# 180Micro_TopLevel.net
KiCad netlist of a schematic drawn in Altium Designer
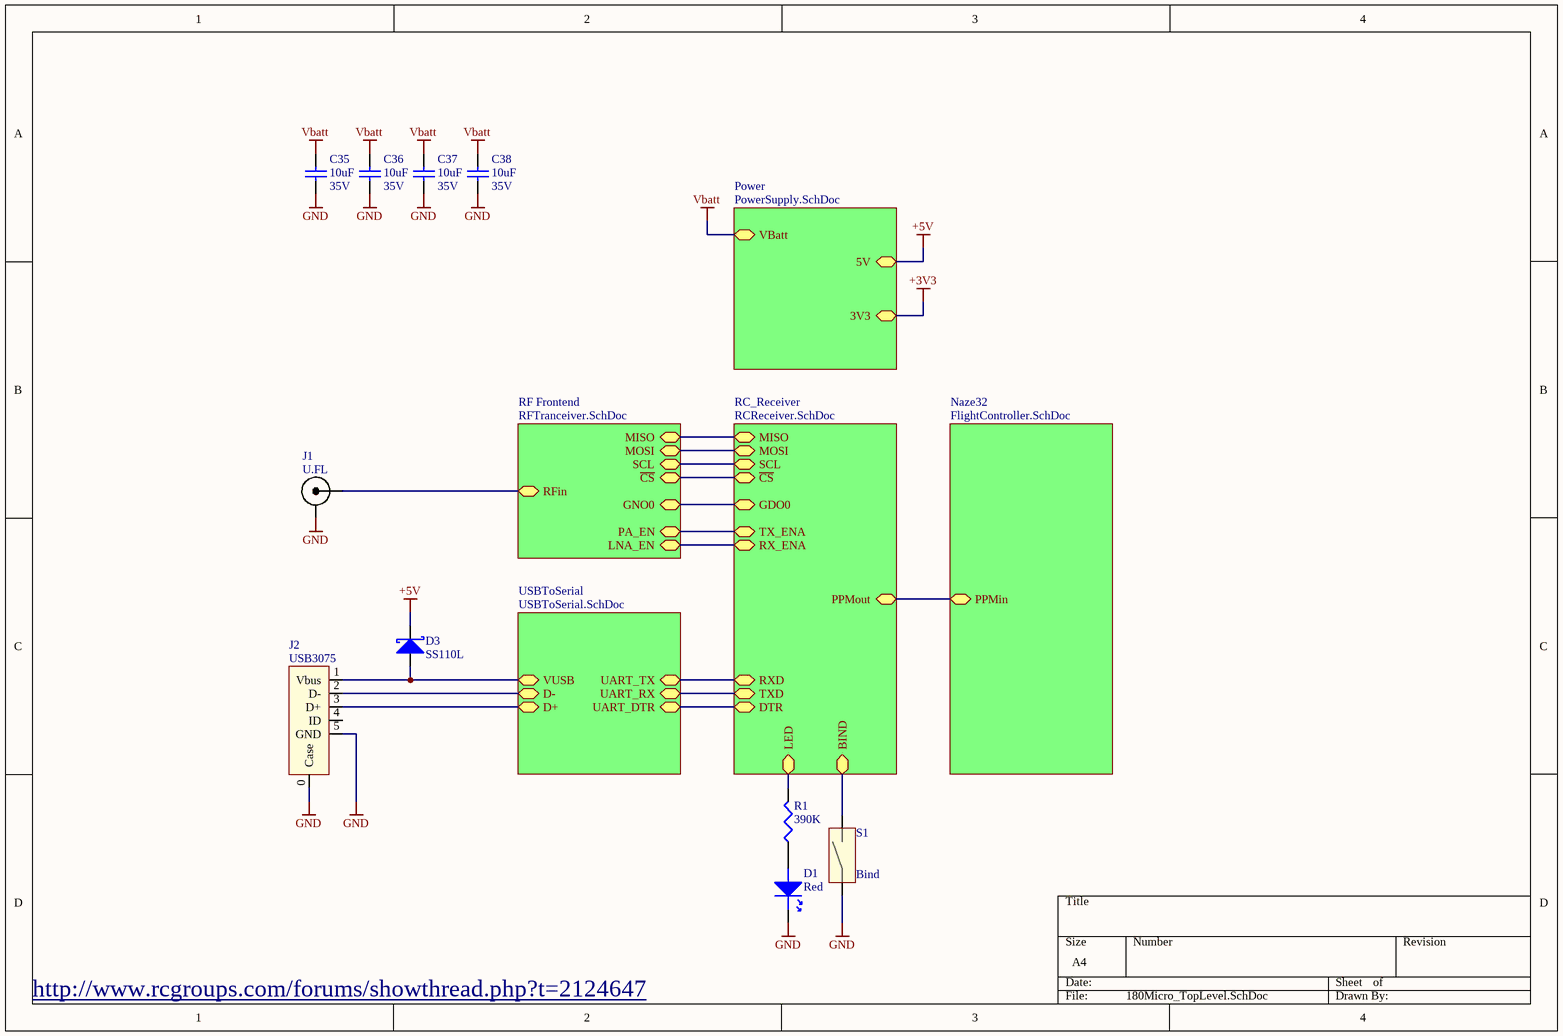
[diagram p0: 180Micro_TopLevel.SchDoc]

(export (version "E")
  (design (tool "Eeschema 10.0.6"))
  (components
    (comp (ref "C35")
      (value "10uF")
      (description "Capacitor, 10uF, 35V, X5R")
      (fields (field (name "VOLTAGE RATING") "35V"))
      (libsource (lib "AR_Capacitors_Ceramic") (part "10uF/1206/CER/35V"))
    )
    (comp (ref "C36")
      (value "10uF")
      (description "Capacitor, 10uF, 35V, X5R")
      (fields (field (name "VOLTAGE RATING") "35V"))
      (libsource (lib "AR_Capacitors_Ceramic") (part "10uF/1206/CER/35V"))
    )
    (comp (ref "C37")
      (value "10uF")
      (description "Capacitor, 10uF, 35V, X5R")
      (fields (field (name "VOLTAGE RATING") "35V"))
      (libsource (lib "AR_Capacitors_Ceramic") (part "10uF/1206/CER/35V"))
    )
    (comp (ref "C38")
      (value "10uF")
      (description "Capacitor, 10uF, 35V, X5R")
      (fields (field (name "VOLTAGE RATING") "35V"))
      (libsource (lib "AR_Capacitors_Ceramic") (part "10uF/1206/CER/35V"))
    )
    (comp (ref "D1")
      (value "Red")
      (footprint "D-0805")
      (description "Led, Red, Li:2.5mcd, Vf:1.8V, If:0.02A")
      (libsource (lib "AR_Misc") (part "SML-211UTT86K"))
    )
    (comp (ref "D3")
      (value "SS110L")
      (footprint "SUB-SMA")
      (description "Diode Schottky, Vrrm: 100V, If: 1A, Vf: 0.9V")
      (libsource (lib "AR_Diodes") (part "SS110L"))
    )
    (comp (ref "J1")
      (value "U.FL")
      (footprint "U_FL")
      (description "Connector RF Coax")
      (libsource (lib "AR_Connectors") (part "U.FL-R-SMT"))
    )
    (comp (ref "J2")
      (value "USB3075")
      (footprint "USB3075")
      (description "USB 2.0 MICRO B, RCPT, 5POS, SMT")
      (libsource (lib "AR_Connectors") (part "USB3075"))
    )
    (comp (ref "R1")
      (value "390K")
      (footprint "0603")
      (description "Resistor, 390K, 1%, 0.1W, 75V, 50PPM, 0603")
      (libsource (lib "AR_Resistors_SMD") (part "390K/0603/0100W/75V"))
    )
    (comp (ref "S1")
      (value "Bind")
      (footprint "KSS")
      (description "Switch, Tactile, SPNO, DC:32V, DC:50mA")
      (libsource (lib "AR_Misc") (part "KSS341G LFS"))
    )
  )
  (nets
    (net (code "2") (name "+5V") (class "Default")
      (node (ref "D3") (pin "2") (pinfunction "K_2") (pintype "passive"))
    )
    (net (code "3") (name "/BIND") (class "Default")
      (node (ref "S1") (pin "2") (pinfunction "2_2") (pintype "passive"))
    )
    (net (code "4") (name "/D+") (class "Default")
      (node (ref "J2") (pin "3") (pinfunction "D+_3") (pintype "passive"))
    )
    (net (code "5") (name "/D-") (class "Default")
      (node (ref "J2") (pin "2") (pinfunction "D-_2") (pintype "passive"))
    )
    (net (code "8") (name "/LED") (class "Default")
      (node (ref "R1") (pin "2") (pinfunction "2_2") (pintype "passive"))
    )
    (net (code "14") (name "/RFin") (class "Default")
      (node (ref "J1") (pin "1") (pinfunction "1_1") (pintype "power_in"))
    )
    (net (code "18") (name "/VUSB") (class "Default")
      (node (ref "D3") (pin "1") (pinfunction "A_1") (pintype "passive"))
      (node (ref "J2") (pin "1") (pinfunction "Vbus_1") (pintype "passive"))
    )
    (net (code "20") (name "GND") (class "Default")
      (node (ref "C35") (pin "1") (pinfunction "1_1") (pintype "passive"))
      (node (ref "C36") (pin "1") (pinfunction "1_1") (pintype "passive"))
      (node (ref "C37") (pin "1") (pinfunction "1_1") (pintype "passive"))
      (node (ref "C38") (pin "1") (pinfunction "1_1") (pintype "passive"))
      (node (ref "D1") (pin "K") (pinfunction "K_K") (pintype "passive"))
      (node (ref "J1") (pin "0") (pinfunction "GND_0") (pintype "power_in"))
      (node (ref "J2") (pin "0") (pinfunction "Case_0") (pintype "passive"))
      (node (ref "J2") (pin "5") (pinfunction "GND_5") (pintype "passive"))
      (node (ref "S1") (pin "1") (pinfunction "1_1") (pintype "passive"))
    )
    (net (code "21") (name "Net-(D1-PadA)") (class "Default")
      (node (ref "D1") (pin "A") (pinfunction "A_A") (pintype "passive"))
      (node (ref "R1") (pin "1") (pinfunction "1_1") (pintype "passive"))
    )
    (net (code "22") (name "Vbatt") (class "Default")
      (node (ref "C35") (pin "2") (pinfunction "2_2") (pintype "passive"))
      (node (ref "C36") (pin "2") (pinfunction "2_2") (pintype "passive"))
      (node (ref "C37") (pin "2") (pinfunction "2_2") (pintype "passive"))
      (node (ref "C38") (pin "2") (pinfunction "2_2") (pintype "passive"))
    )
    (net (code "23") (name "unconnected-(J2-ID-Pad4)") (class "Default")
      (node (ref "J2") (pin "4") (pinfunction "ID_4") (pintype "passive"))
    )
  )
)
